# cpu.net
KiCad netlist of a schematic drawn in Altium Designer
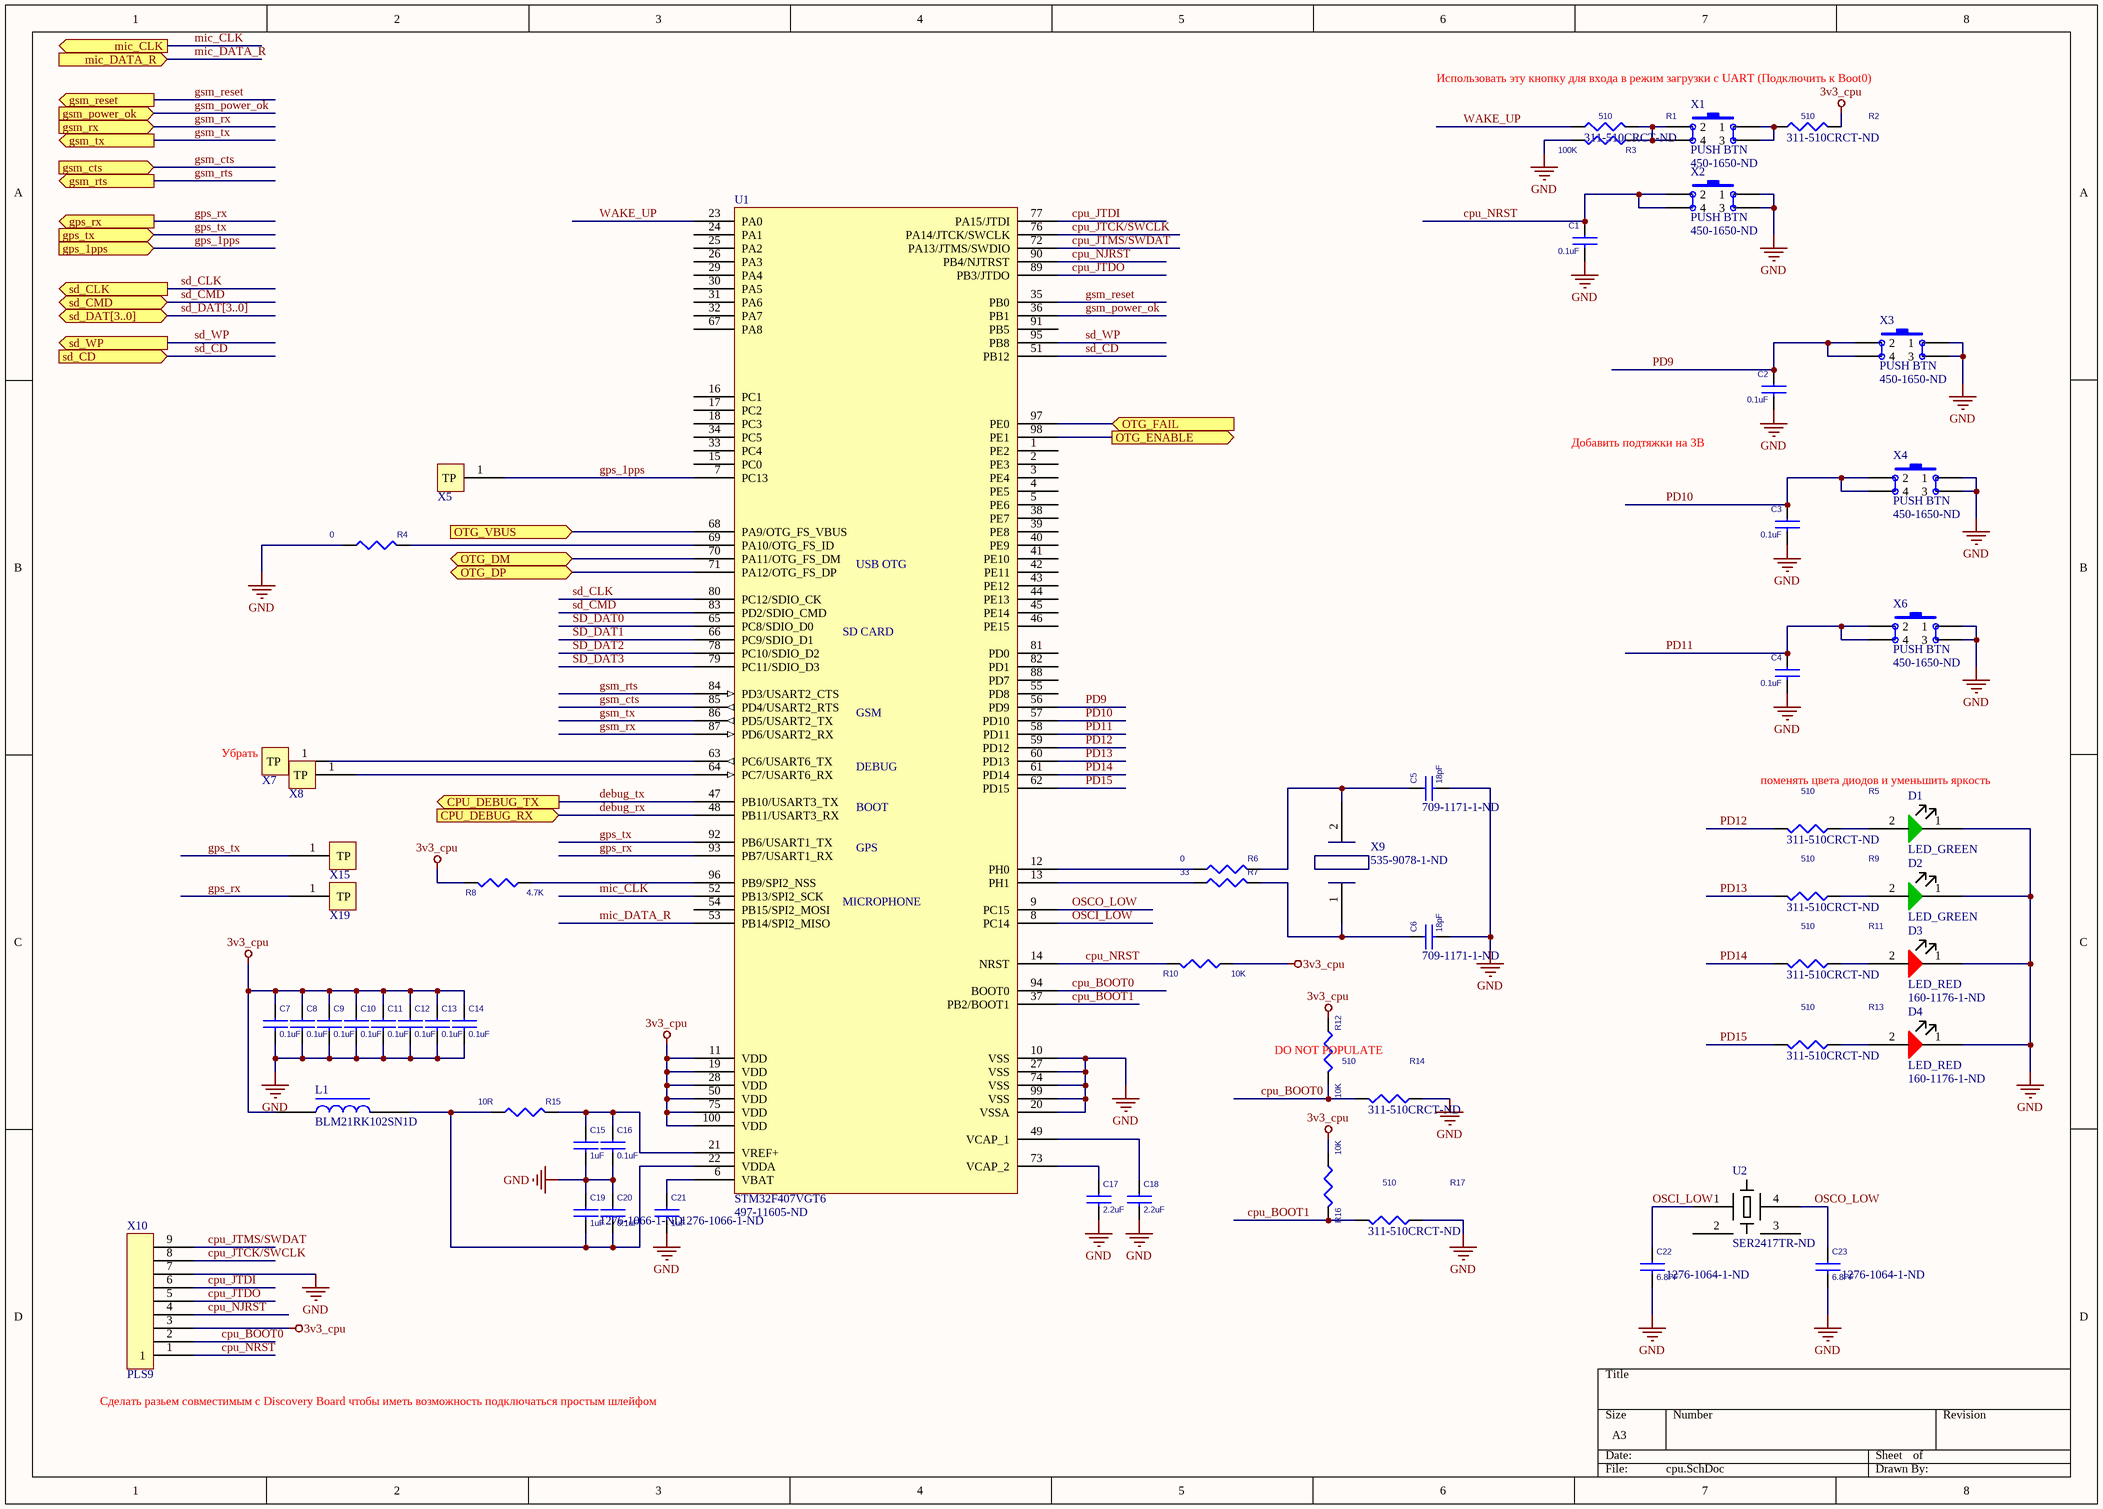
[diagram p0: cpu.SchDoc]

(export (version "E")
  (design (tool "Eeschema 10.0.6"))
  (components
    (comp (ref "C1")
      (value "0.1uF")
      (footprint "CAPC2012X09M")
      (description "CAP CER 0.1UF 25V 10% X7R 0805")
      (libsource (lib "Capacitors") (part "CAP_SMD_0.1UF_10%"))
    )
    (comp (ref "C2")
      (value "0.1uF")
      (footprint "CAPC2012X09M")
      (description "CAP CER 0.1UF 25V 10% X7R 0805")
      (libsource (lib "Capacitors") (part "CAP_SMD_0.1UF_10%"))
    )
    (comp (ref "C3")
      (value "0.1uF")
      (footprint "CAPC2012X09M")
      (description "CAP CER 0.1UF 25V 10% X7R 0805")
      (libsource (lib "Capacitors") (part "CAP_SMD_0.1UF_10%"))
    )
    (comp (ref "C4")
      (value "0.1uF")
      (footprint "CAPC2012X09M")
      (description "CAP CER 0.1UF 25V 10% X7R 0805")
      (libsource (lib "Capacitors") (part "CAP_SMD_0.1UF_10%"))
    )
    (comp (ref "C5")
      (value "18pF")
      (footprint "CAPC2012X09M")
      (description "CAP CER 27PF 200V 5% NP0 0805")
      (fields (field (name "SUPPLIER PART NUMBER 1") "709-1171-1-ND"))
      (libsource (lib "Capacitors") (part "CAP_SMD_18PF_5%"))
    )
    (comp (ref "C6")
      (value "18pF")
      (footprint "CAPC2012X09M")
      (description "CAP CER 27PF 200V 5% NP0 0805")
      (fields (field (name "SUPPLIER PART NUMBER 1") "709-1171-1-ND"))
      (libsource (lib "Capacitors") (part "CAP_SMD_18PF_5%"))
    )
    (comp (ref "C7")
      (value "0.1uF")
      (footprint "CAPC2012X09M")
      (description "CAP CER 0.1UF 25V 10% X7R 0805")
      (libsource (lib "Capacitors") (part "CAP_SMD_0.1UF_10%"))
    )
    (comp (ref "C8")
      (value "0.1uF")
      (footprint "CAPC2012X09M")
      (description "CAP CER 0.1UF 25V 10% X7R 0805")
      (libsource (lib "Capacitors") (part "CAP_SMD_0.1UF_10%"))
    )
    (comp (ref "C9")
      (value "0.1uF")
      (footprint "CAPC2012X09M")
      (description "CAP CER 0.1UF 25V 10% X7R 0805")
      (libsource (lib "Capacitors") (part "CAP_SMD_0.1UF_10%"))
    )
    (comp (ref "C10")
      (value "0.1uF")
      (footprint "CAPC2012X09M")
      (description "CAP CER 0.1UF 25V 10% X7R 0805")
      (libsource (lib "Capacitors") (part "CAP_SMD_0.1UF_10%"))
    )
    (comp (ref "C11")
      (value "0.1uF")
      (footprint "CAPC2012X09M")
      (description "CAP CER 0.1UF 25V 10% X7R 0805")
      (libsource (lib "Capacitors") (part "CAP_SMD_0.1UF_10%"))
    )
    (comp (ref "C12")
      (value "0.1uF")
      (footprint "CAPC2012X09M")
      (description "CAP CER 0.1UF 25V 10% X7R 0805")
      (libsource (lib "Capacitors") (part "CAP_SMD_0.1UF_10%"))
    )
    (comp (ref "C13")
      (value "0.1uF")
      (footprint "CAPC2012X09M")
      (description "CAP CER 0.1UF 25V 10% X7R 0805")
      (libsource (lib "Capacitors") (part "CAP_SMD_0.1UF_10%"))
    )
    (comp (ref "C14")
      (value "0.1uF")
      (footprint "CAPC2012X09M")
      (description "CAP CER 0.1UF 25V 10% X7R 0805")
      (libsource (lib "Capacitors") (part "CAP_SMD_0.1UF_10%"))
    )
    (comp (ref "C15")
      (value "1uF")
      (footprint "CAPC2012X09M")
      (description "MLCC; 1uF; 25V; X7R; ±10%; SMD; 0805;")
      (libsource (lib "Capacitors") (part "CAP_SMD_1uF_10%"))
    )
    (comp (ref "C16")
      (value "0.1uF")
      (footprint "CAPC2012X09M")
      (description "CAP CER 0.1UF 25V 10% X7R 0805")
      (libsource (lib "Capacitors") (part "CAP_SMD_0.1UF_10%"))
    )
    (comp (ref "C17")
      (value "2.2uF")
      (footprint "CAPC2012X09M")
      (description "CAP CER 2.2UF 16V 10% X5R 0805")
      (libsource (lib "Capacitors") (part "CAP_SMD_2.2uF_10%"))
    )
    (comp (ref "C18")
      (value "2.2uF")
      (footprint "CAPC2012X09M")
      (description "CAP CER 2.2UF 16V 10% X5R 0805")
      (libsource (lib "Capacitors") (part "CAP_SMD_2.2uF_10%"))
    )
    (comp (ref "C19")
      (value "1uF")
      (footprint "CAPC2012X09M")
      (description "MLCC; 1uF; 25V; X7R; ±10%; SMD; 0805;")
      (fields (field (name "SUPPLIER PART NUMBER 1") "1276-1066-1-ND"))
      (libsource (lib "Capacitors") (part "CAP_SMD_1uF_10%"))
    )
    (comp (ref "C20")
      (value "0.1uF")
      (footprint "CAPC2012X09M")
      (description "CAP CER 0.1UF 25V 10% X7R 0805")
      (libsource (lib "Capacitors") (part "CAP_SMD_0.1UF_10%"))
    )
    (comp (ref "C21")
      (value "1uF")
      (footprint "CAPC2012X09M")
      (description "MLCC; 1uF; 25V; X7R; ±10%; SMD; 0805;")
      (fields (field (name "SUPPLIER PART NUMBER 1") "1276-1066-1-ND"))
      (libsource (lib "Capacitors") (part "CAP_SMD_1uF_10%"))
    )
    (comp (ref "C22")
      (value "6.8PF")
      (footprint "CAPC2012X09M")
      (description "CAP MLCC 6.8PF 50V 5% NP0 0805")
      (fields (field (name "SUPPLIER PART NUMBER 1") "1276-1064-1-ND"))
      (libsource (lib "Capacitors") (part "CAP_SMD_6.8PF_5%"))
    )
    (comp (ref "C23")
      (value "6.8PF")
      (footprint "CAPC2012X09M")
      (description "CAP MLCC 6.8PF 50V 5% NP0 0805")
      (fields (field (name "SUPPLIER PART NUMBER 1") "1276-1064-1-ND"))
      (libsource (lib "Capacitors") (part "CAP_SMD_6.8PF_5%"))
    )
    (comp (ref "D1")
      (value "LED_GREEN")
      (footprint "DIOC2012X11N")
      (libsource (lib "Passive") (part "LED_GREEN"))
    )
    (comp (ref "D2")
      (value "LED_GREEN")
      (footprint "DIOC2012X11N")
      (libsource (lib "Passive") (part "LED_GREEN"))
    )
    (comp (ref "D3")
      (value "LED_RED")
      (footprint "DIOC2012X11N")
      (fields (field (name "SUPPLIER PART NUMBER 1") "160-1176-1-ND"))
      (libsource (lib "Passive") (part "LED_RED"))
    )
    (comp (ref "D4")
      (value "LED_RED")
      (footprint "DIOC2012X11N")
      (fields (field (name "SUPPLIER PART NUMBER 1") "160-1176-1-ND"))
      (libsource (lib "Passive") (part "LED_RED"))
    )
    (comp (ref "L1")
      (value "BLM21RK102SN1D")
      (footprint "DIOC2012X11N")
      (libsource (lib "Passive") (part "BLM21RK102SN1D"))
    )
    (comp (ref "R1")
      (value "510")
      (footprint "RESC2013X06M")
      (description "RES - 510 OHM, 5%, 1/8W, 0805 SMD")
      (fields (field (name "SUPPLIER PART NUMBER 1") "311-510CRCT-ND"))
      (libsource (lib "Resistors") (part "RES_SMD_510_5%"))
    )
    (comp (ref "R2")
      (value "510")
      (footprint "RESC2013X06M")
      (description "RES - 510 OHM, 5%, 1/8W, 0805 SMD")
      (fields (field (name "SUPPLIER PART NUMBER 1") "311-510CRCT-ND"))
      (libsource (lib "Resistors") (part "RES_SMD_510_5%"))
    )
    (comp (ref "R3")
      (value "100K")
      (footprint "RESC2013X06M")
      (description "RES - 100K OHM, 5%, 1/8W, 0805 SMD")
      (libsource (lib "Resistors") (part "RES_SMD_100K"))
    )
    (comp (ref "R4")
      (value "0")
      (footprint "RESC2013X06M")
      (description "RES 0.0 OHM 1/8W JUMP 0805 SMD")
      (libsource (lib "Resistors") (part "RES_SMD_0"))
    )
    (comp (ref "R5")
      (value "510")
      (footprint "RESC2013X06M")
      (description "RES - 510 OHM, 5%, 1/8W, 0805 SMD")
      (fields (field (name "SUPPLIER PART NUMBER 1") "311-510CRCT-ND"))
      (libsource (lib "Resistors") (part "RES_SMD_510_5%"))
    )
    (comp (ref "R6")
      (value "0")
      (footprint "RESC2013X06M")
      (description "RES 0.0 OHM 1/8W JUMP 0805 SMD")
      (libsource (lib "Resistors") (part "RES_SMD_0"))
    )
    (comp (ref "R7")
      (value "33")
      (footprint "RESC2013X06M")
      (description "RES - 33 OHM, 5%, 1/8W, 0805 SMD")
      (libsource (lib "Resistors") (part "RES_SMD_33R_5%"))
    )
    (comp (ref "R8")
      (value "4.7K")
      (footprint "RESC2013X06M")
      (description "RES 4.7K OHM 1/8W 1% 0805 SMD")
      (libsource (lib "Resistors") (part "RES_SMD_4.7K_1%"))
    )
    (comp (ref "R9")
      (value "510")
      (footprint "RESC2013X06M")
      (description "RES - 510 OHM, 5%, 1/8W, 0805 SMD")
      (fields (field (name "SUPPLIER PART NUMBER 1") "311-510CRCT-ND"))
      (libsource (lib "Resistors") (part "RES_SMD_510_5%"))
    )
    (comp (ref "R10")
      (value "10K")
      (footprint "RESC2013X06M")
      (description "RES 10K OHM 1/8W 5% 0805 SMD")
      (libsource (lib "Resistors") (part "RES_SMD_10K_5%"))
    )
    (comp (ref "R11")
      (value "510")
      (footprint "RESC2013X06M")
      (description "RES - 510 OHM, 5%, 1/8W, 0805 SMD")
      (fields (field (name "SUPPLIER PART NUMBER 1") "311-510CRCT-ND"))
      (libsource (lib "Resistors") (part "RES_SMD_510_5%"))
    )
    (comp (ref "R12")
      (value "10K")
      (footprint "RESC2013X06M")
      (description "RES 10K OHM 1/8W 5% 0805 SMD")
      (libsource (lib "Resistors") (part "RES_SMD_10K_5%"))
    )
    (comp (ref "R13")
      (value "510")
      (footprint "RESC2013X06M")
      (description "RES - 510 OHM, 5%, 1/8W, 0805 SMD")
      (fields (field (name "SUPPLIER PART NUMBER 1") "311-510CRCT-ND"))
      (libsource (lib "Resistors") (part "RES_SMD_510_5%"))
    )
    (comp (ref "R14")
      (value "510")
      (footprint "RESC2013X06M")
      (description "RES - 510 OHM, 5%, 1/8W, 0805 SMD")
      (fields (field (name "SUPPLIER PART NUMBER 1") "311-510CRCT-ND"))
      (libsource (lib "Resistors") (part "RES_SMD_510_5%"))
    )
    (comp (ref "R15")
      (value "10R")
      (footprint "RESC2013X06M")
      (description "RES 10 OHM 1/8W 1% 0805 SMD")
      (libsource (lib "Resistors") (part "RES_SMD_10R_5%"))
    )
    (comp (ref "R16")
      (value "10K")
      (footprint "RESC2013X06M")
      (description "RES 10K OHM 1/8W 5% 0805 SMD")
      (libsource (lib "Resistors") (part "RES_SMD_10K_5%"))
    )
    (comp (ref "R17")
      (value "510")
      (footprint "RESC2013X06M")
      (description "RES - 510 OHM, 5%, 1/8W, 0805 SMD")
      (fields (field (name "SUPPLIER PART NUMBER 1") "311-510CRCT-ND"))
      (libsource (lib "Resistors") (part "RES_SMD_510_5%"))
    )
    (comp (ref "U1")
      (value "STM32F407VGT6")
      (footprint "TSQFP50P1600X1600X160-100M")
      (fields (field (name "SUPPLIER PART NUMBER 1") "497-11605-ND"))
      (libsource (lib "TruthEar") (part "STM32F407VGT6"))
    )
    (comp (ref "U2")
      (value "32.768KHZ")
      (footprint "SOJ550P380X254-4M")
      (fields (field (name "SUPPLIER PART NUMBER 1") "SER2417TR-ND"))
      (libsource (lib "TruthEar") (part "MC-306"))
    )
    (comp (ref "X1")
      (value "PUSH BTN")
      (footprint "PUSHBTN")
      (fields (field (name "SUPPLIER PART NUMBER 1") "450-1650-ND"))
      (libsource (lib "TruthEar") (part "SW1"))
    )
    (comp (ref "X2")
      (value "PUSH BTN")
      (footprint "PUSHBTN")
      (fields (field (name "SUPPLIER PART NUMBER 1") "450-1650-ND"))
      (libsource (lib "TruthEar") (part "SW1"))
    )
    (comp (ref "X3")
      (value "PUSH BTN")
      (footprint "PUSHBTN")
      (fields (field (name "SUPPLIER PART NUMBER 1") "450-1650-ND"))
      (libsource (lib "TruthEar") (part "SW1"))
    )
    (comp (ref "X4")
      (value "PUSH BTN")
      (footprint "PUSHBTN")
      (fields (field (name "SUPPLIER PART NUMBER 1") "450-1650-ND"))
      (libsource (lib "TruthEar") (part "SW1"))
    )
    (comp (ref "X5") (value "TestPoint") (footprint "TP") (libsource (lib "") (part "TestPoint_2")))
    (comp (ref "X6")
      (value "PUSH BTN")
      (footprint "PUSHBTN")
      (fields (field (name "SUPPLIER PART NUMBER 1") "450-1650-ND"))
      (libsource (lib "TruthEar") (part "SW1"))
    )
    (comp (ref "X7") (value "TestPoint") (footprint "TP") (libsource (lib "Passive") (part "TestPoint")))
    (comp (ref "X8") (value "TestPoint") (footprint "TP") (libsource (lib "Passive") (part "TestPoint")))
    (comp (ref "X9")
      (value "25.000Mhz")
      (footprint "SODFL1270X420-2L")
      (fields (field (name "SUPPLIER PART NUMBER 1") "535-9078-1-ND"))
      (libsource (lib "TruthEar") (part "OSC25M"))
    )
    (comp (ref "X10") (value "PLS9") (footprint "PLS9") (libsource (lib "Connectors") (part "PLS9")))
    (comp (ref "X15") (value "TestPoint") (footprint "TP") (libsource (lib "") (part "TestPoint_1")))
    (comp (ref "X19") (value "TestPoint") (footprint "TP") (libsource (lib "") (part "TestPoint_1")))
  )
  (nets
    (net (code "5") (name "/OSCI_LOW") (class "Default")
      (node (ref "C22") (pin "1") (pinfunction "1_1") (pintype "passive"))
      (node (ref "U1") (pin "8") (pinfunction "PC14_8") (pintype "passive"))
      (node (ref "U2") (pin "1") (pinfunction "OSC1_1") (pintype "power_in"))
    )
    (net (code "6") (name "/OSCO_LOW") (class "Default")
      (node (ref "C23") (pin "1") (pinfunction "1_1") (pintype "passive"))
      (node (ref "U1") (pin "9") (pinfunction "PC15_9") (pintype "passive"))
      (node (ref "U2") (pin "4") (pinfunction "OSC2_4") (pintype "power_in"))
    )
    (net (code "7") (name "/OTG_DM") (class "Default")
      (node (ref "U1") (pin "70") (pinfunction "PA11/OTG_FS_DM_70") (pintype "passive"))
    )
    (net (code "8") (name "/OTG_DP") (class "Default")
      (node (ref "U1") (pin "71") (pinfunction "PA12/OTG_FS_DP_71") (pintype "passive"))
    )
    (net (code "9") (name "/OTG_ENABLE") (class "Default")
      (node (ref "U1") (pin "98") (pinfunction "PE1_98") (pintype "passive"))
    )
    (net (code "10") (name "/OTG_FAIL") (class "Default")
      (node (ref "U1") (pin "97") (pinfunction "PE0_97") (pintype "passive"))
    )
    (net (code "11") (name "/OTG_VBUS") (class "Default")
      (node (ref "U1") (pin "68") (pinfunction "PA9/OTG_FS_VBUS_68") (pintype "passive"))
    )
    (net (code "12") (name "/PD9") (class "Default")
      (node (ref "C2") (pin "1") (pinfunction "1_1") (pintype "passive"))
      (node (ref "U1") (pin "56") (pinfunction "PD9_56") (pintype "passive"))
      (node (ref "X3") (pin "2") (pinfunction "2_2") (pintype "passive"))
      (node (ref "X3") (pin "4") (pinfunction "4_4") (pintype "passive"))
    )
    (net (code "13") (name "/PD10") (class "Default")
      (node (ref "C3") (pin "1") (pinfunction "1_1") (pintype "passive"))
      (node (ref "U1") (pin "57") (pinfunction "PD10_57") (pintype "passive"))
      (node (ref "X4") (pin "2") (pinfunction "2_2") (pintype "passive"))
      (node (ref "X4") (pin "4") (pinfunction "4_4") (pintype "passive"))
    )
    (net (code "14") (name "/PD11") (class "Default")
      (node (ref "C4") (pin "1") (pinfunction "1_1") (pintype "passive"))
      (node (ref "U1") (pin "58") (pinfunction "PD11_58") (pintype "passive"))
      (node (ref "X6") (pin "2") (pinfunction "2_2") (pintype "passive"))
      (node (ref "X6") (pin "4") (pinfunction "4_4") (pintype "passive"))
    )
    (net (code "15") (name "/PD12") (class "Default")
      (node (ref "R5") (pin "2") (pinfunction "2_2") (pintype "passive"))
      (node (ref "U1") (pin "59") (pinfunction "PD12_59") (pintype "passive"))
    )
    (net (code "16") (name "/PD13") (class "Default")
      (node (ref "R9") (pin "2") (pinfunction "2_2") (pintype "passive"))
      (node (ref "U1") (pin "60") (pinfunction "PD13_60") (pintype "passive"))
    )
    (net (code "17") (name "/PD14") (class "Default")
      (node (ref "R11") (pin "2") (pinfunction "2_2") (pintype "passive"))
      (node (ref "U1") (pin "61") (pinfunction "PD14_61") (pintype "passive"))
    )
    (net (code "18") (name "/PD15") (class "Default")
      (node (ref "R13") (pin "2") (pinfunction "2_2") (pintype "passive"))
      (node (ref "U1") (pin "62") (pinfunction "PD15_62") (pintype "passive"))
    )
    (net (code "19") (name "/SD_DAT0") (class "Default")
      (node (ref "U1") (pin "65") (pinfunction "PC8/SDIO_D0_65") (pintype "passive"))
    )
    (net (code "20") (name "/SD_DAT1") (class "Default")
      (node (ref "U1") (pin "66") (pinfunction "PC9/SDIO_D1_66") (pintype "passive"))
    )
    (net (code "21") (name "/SD_DAT2") (class "Default")
      (node (ref "U1") (pin "78") (pinfunction "PC10/SDIO_D2_78") (pintype "passive"))
    )
    (net (code "22") (name "/SD_DAT3") (class "Default")
      (node (ref "U1") (pin "79") (pinfunction "PC11/SDIO_D3_79") (pintype "passive"))
    )
    (net (code "23") (name "/WAKE_UP") (class "Default")
      (node (ref "R1") (pin "2") (pinfunction "2_2") (pintype "passive"))
      (node (ref "U1") (pin "23") (pinfunction "PA0_23") (pintype "passive"))
    )
    (net (code "24") (name "/cpu_BOOT0") (class "Default")
      (node (ref "R12") (pin "1") (pinfunction "1_1") (pintype "passive"))
      (node (ref "R14") (pin "1") (pinfunction "1_1") (pintype "passive"))
      (node (ref "U1") (pin "94") (pinfunction "BOOT0_94") (pintype "passive"))
      (node (ref "X10") (pin "2") (pinfunction "2_2") (pintype "power_in"))
    )
    (net (code "25") (name "/cpu_BOOT1") (class "Default")
      (node (ref "R16") (pin "2") (pinfunction "2_2") (pintype "passive"))
      (node (ref "R17") (pin "2") (pinfunction "2_2") (pintype "passive"))
      (node (ref "U1") (pin "37") (pinfunction "PB2/BOOT1_37") (pintype "passive"))
    )
    (net (code "26") (name "/cpu_JTCK{slash}SWCLK") (class "Default")
      (node (ref "U1") (pin "76") (pinfunction "PA14/JTCK/SWCLK_76") (pintype "passive"))
      (node (ref "X10") (pin "8") (pinfunction "8_8") (pintype "power_in"))
    )
    (net (code "27") (name "/cpu_JTDI") (class "Default")
      (node (ref "U1") (pin "77") (pinfunction "PA15/JTDI_77") (pintype "passive"))
      (node (ref "X10") (pin "6") (pinfunction "6_6") (pintype "power_in"))
    )
    (net (code "28") (name "/cpu_JTDO") (class "Default")
      (node (ref "U1") (pin "89") (pinfunction "PB3/JTDO_89") (pintype "passive"))
      (node (ref "X10") (pin "5") (pinfunction "5_5") (pintype "power_in"))
    )
    (net (code "29") (name "/cpu_JTMS{slash}SWDAT") (class "Default")
      (node (ref "U1") (pin "72") (pinfunction "PA13/JTMS/SWDIO_72") (pintype "passive"))
      (node (ref "X10") (pin "9") (pinfunction "9_9") (pintype "power_in"))
    )
    (net (code "30") (name "/cpu_NJRST") (class "Default")
      (node (ref "U1") (pin "90") (pinfunction "PB4/NJTRST_90") (pintype "passive"))
      (node (ref "X10") (pin "4") (pinfunction "4_4") (pintype "power_in"))
    )
    (net (code "31") (name "/cpu_NRST") (class "Default")
      (node (ref "C1") (pin "1") (pinfunction "1_1") (pintype "passive"))
      (node (ref "R10") (pin "2") (pinfunction "2_2") (pintype "passive"))
      (node (ref "U1") (pin "14") (pinfunction "NRST_14") (pintype "passive"))
      (node (ref "X10") (pin "1") (pinfunction "1_1") (pintype "power_in"))
      (node (ref "X2") (pin "2") (pinfunction "2_2") (pintype "passive"))
      (node (ref "X2") (pin "4") (pinfunction "4_4") (pintype "passive"))
    )
    (net (code "32") (name "/debug_rx") (class "Default")
      (node (ref "U1") (pin "48") (pinfunction "PB11/USART3_RX_48") (pintype "passive"))
    )
    (net (code "33") (name "/debug_tx") (class "Default")
      (node (ref "U1") (pin "47") (pinfunction "PB10/USART3_TX_47") (pintype "passive"))
    )
    (net (code "34") (name "/gps_1pps") (class "Default")
      (node (ref "U1") (pin "7") (pinfunction "PC13_7") (pintype "passive"))
      (node (ref "X5") (pin "1") (pinfunction "TP_1") (pintype "power_in"))
    )
    (net (code "35") (name "/gps_rx") (class "Default")
      (node (ref "U1") (pin "93") (pinfunction "PB7/USART1_RX_93") (pintype "passive"))
      (node (ref "X19") (pin "1") (pinfunction "TP_1") (pintype "power_in"))
    )
    (net (code "36") (name "/gps_tx") (class "Default")
      (node (ref "U1") (pin "92") (pinfunction "PB6/USART1_TX_92") (pintype "passive"))
      (node (ref "X15") (pin "1") (pinfunction "TP_1") (pintype "power_in"))
    )
    (net (code "37") (name "/gsm_cts") (class "Default")
      (node (ref "U1") (pin "85") (pinfunction "PD4/USART2_RTS_85") (pintype "output"))
    )
    (net (code "38") (name "/gsm_power_ok") (class "Default")
      (node (ref "U1") (pin "36") (pinfunction "PB1_36") (pintype "passive"))
    )
    (net (code "39") (name "/gsm_reset") (class "Default")
      (node (ref "U1") (pin "35") (pinfunction "PB0_35") (pintype "passive"))
    )
    (net (code "40") (name "/gsm_rts") (class "Default")
      (node (ref "U1") (pin "84") (pinfunction "PD3/USART2_CTS_84") (pintype "input"))
    )
    (net (code "41") (name "/gsm_rx") (class "Default")
      (node (ref "U1") (pin "87") (pinfunction "PD6/USART2_RX_87") (pintype "input"))
    )
    (net (code "42") (name "/gsm_tx") (class "Default")
      (node (ref "U1") (pin "86") (pinfunction "PD5/USART2_TX_86") (pintype "output"))
    )
    (net (code "43") (name "/mic_CLK") (class "Default")
      (node (ref "U1") (pin "52") (pinfunction "PB13/SPI2_SCK_52") (pintype "passive"))
    )
    (net (code "44") (name "/mic_DATA_R") (class "Default")
      (node (ref "U1") (pin "53") (pinfunction "PB14/SPI2_MISO_53") (pintype "passive"))
    )
    (net (code "45") (name "/sd_CD") (class "Default")
      (node (ref "U1") (pin "51") (pinfunction "PB12_51") (pintype "passive"))
    )
    (net (code "46") (name "/sd_CLK") (class "Default")
      (node (ref "U1") (pin "80") (pinfunction "PC12/SDIO_CK_80") (pintype "passive"))
    )
    (net (code "47") (name "/sd_CMD") (class "Default")
      (node (ref "U1") (pin "83") (pinfunction "PD2/SDIO_CMD_83") (pintype "passive"))
    )
    (net (code "49") (name "/sd_WP") (class "Default")
      (node (ref "U1") (pin "95") (pinfunction "PB8_95") (pintype "passive"))
    )
    (net (code "50") (name "3v3_cpu") (class "Default")
      (node (ref "C10") (pin "1") (pinfunction "1_1") (pintype "passive"))
      (node (ref "C11") (pin "1") (pinfunction "1_1") (pintype "passive"))
      (node (ref "C12") (pin "1") (pinfunction "1_1") (pintype "passive"))
      (node (ref "C13") (pin "1") (pinfunction "1_1") (pintype "passive"))
      (node (ref "C14") (pin "1") (pinfunction "1_1") (pintype "passive"))
      (node (ref "C7") (pin "1") (pinfunction "1_1") (pintype "passive"))
      (node (ref "C8") (pin "1") (pinfunction "1_1") (pintype "passive"))
      (node (ref "C9") (pin "1") (pinfunction "1_1") (pintype "passive"))
      (node (ref "L1") (pin "1") (pinfunction "1_1") (pintype "passive"))
      (node (ref "R10") (pin "1") (pinfunction "1_1") (pintype "passive"))
      (node (ref "R12") (pin "2") (pinfunction "2_2") (pintype "passive"))
      (node (ref "R16") (pin "1") (pinfunction "1_1") (pintype "passive"))
      (node (ref "R2") (pin "1") (pinfunction "1_1") (pintype "passive"))
      (node (ref "R8") (pin "2") (pinfunction "2_2") (pintype "passive"))
      (node (ref "U1") (pin "100") (pinfunction "VDD_100") (pintype "passive"))
      (node (ref "U1") (pin "11") (pinfunction "VDD_11") (pintype "passive"))
      (node (ref "U1") (pin "19") (pinfunction "VDD_19") (pintype "passive"))
      (node (ref "U1") (pin "28") (pinfunction "VDD_28") (pintype "passive"))
      (node (ref "U1") (pin "50") (pinfunction "VDD_50") (pintype "passive"))
      (node (ref "U1") (pin "75") (pinfunction "VDD_75") (pintype "passive"))
      (node (ref "X10") (pin "3") (pinfunction "3_3") (pintype "power_in"))
    )
    (net (code "51") (name "GND") (class "Default")
      (node (ref "C1") (pin "2") (pinfunction "2_2") (pintype "passive"))
      (node (ref "C10") (pin "2") (pinfunction "2_2") (pintype "passive"))
      (node (ref "C11") (pin "2") (pinfunction "2_2") (pintype "passive"))
      (node (ref "C12") (pin "2") (pinfunction "2_2") (pintype "passive"))
      (node (ref "C13") (pin "2") (pinfunction "2_2") (pintype "passive"))
      (node (ref "C14") (pin "2") (pinfunction "2_2") (pintype "passive"))
      (node (ref "C15") (pin "2") (pinfunction "2_2") (pintype "passive"))
      (node (ref "C16") (pin "2") (pinfunction "2_2") (pintype "passive"))
      (node (ref "C17") (pin "2") (pinfunction "2_2") (pintype "passive"))
      (node (ref "C18") (pin "2") (pinfunction "2_2") (pintype "passive"))
      (node (ref "C19") (pin "1") (pinfunction "1_1") (pintype "passive"))
      (node (ref "C2") (pin "2") (pinfunction "2_2") (pintype "passive"))
      (node (ref "C20") (pin "1") (pinfunction "1_1") (pintype "passive"))
      (node (ref "C21") (pin "2") (pinfunction "2_2") (pintype "passive"))
      (node (ref "C22") (pin "2") (pinfunction "2_2") (pintype "passive"))
      (node (ref "C23") (pin "2") (pinfunction "2_2") (pintype "passive"))
      (node (ref "C3") (pin "2") (pinfunction "2_2") (pintype "passive"))
      (node (ref "C4") (pin "2") (pinfunction "2_2") (pintype "passive"))
      (node (ref "C5") (pin "2") (pinfunction "2_2") (pintype "passive"))
      (node (ref "C6") (pin "2") (pinfunction "2_2") (pintype "passive"))
      (node (ref "C7") (pin "2") (pinfunction "2_2") (pintype "passive"))
      (node (ref "C8") (pin "2") (pinfunction "2_2") (pintype "passive"))
      (node (ref "C9") (pin "2") (pinfunction "2_2") (pintype "passive"))
      (node (ref "D1") (pin "1") (pinfunction "C_1") (pintype "passive"))
      (node (ref "D2") (pin "1") (pinfunction "C_1") (pintype "passive"))
      (node (ref "D3") (pin "1") (pinfunction "C_1") (pintype "passive"))
      (node (ref "D4") (pin "1") (pinfunction "C_1") (pintype "passive"))
      (node (ref "R14") (pin "2") (pinfunction "2_2") (pintype "passive"))
      (node (ref "R17") (pin "1") (pinfunction "1_1") (pintype "passive"))
      (node (ref "R3") (pin "1") (pinfunction "1_1") (pintype "passive"))
      (node (ref "R4") (pin "1") (pinfunction "1_1") (pintype "passive"))
      (node (ref "U1") (pin "10") (pinfunction "VSS_10") (pintype "passive"))
      (node (ref "U1") (pin "20") (pinfunction "VSSA_20") (pintype "passive"))
      (node (ref "U1") (pin "27") (pinfunction "VSS_27") (pintype "passive"))
      (node (ref "U1") (pin "74") (pinfunction "VSS_74") (pintype "passive"))
      (node (ref "U1") (pin "99") (pinfunction "VSS_99") (pintype "passive"))
      (node (ref "X10") (pin "7") (pinfunction "7_7") (pintype "power_in"))
      (node (ref "X2") (pin "1") (pinfunction "1_1") (pintype "passive"))
      (node (ref "X2") (pin "3") (pinfunction "3_3") (pintype "passive"))
      (node (ref "X3") (pin "1") (pinfunction "1_1") (pintype "passive"))
      (node (ref "X3") (pin "3") (pinfunction "3_3") (pintype "passive"))
      (node (ref "X4") (pin "1") (pinfunction "1_1") (pintype "passive"))
      (node (ref "X4") (pin "3") (pinfunction "3_3") (pintype "passive"))
      (node (ref "X6") (pin "1") (pinfunction "1_1") (pintype "passive"))
      (node (ref "X6") (pin "3") (pinfunction "3_3") (pintype "passive"))
    )
    (net (code "52") (name "Net-(C5-Pad1)") (class "Default")
      (node (ref "C5") (pin "1") (pinfunction "1_1") (pintype "passive"))
      (node (ref "R6") (pin "2") (pinfunction "2_2") (pintype "passive"))
      (node (ref "X9") (pin "2") (pinfunction "2_2") (pintype "power_in"))
    )
    (net (code "53") (name "Net-(C6-Pad1)") (class "Default")
      (node (ref "C6") (pin "1") (pinfunction "1_1") (pintype "passive"))
      (node (ref "R7") (pin "2") (pinfunction "2_2") (pintype "passive"))
      (node (ref "X9") (pin "1") (pinfunction "1_1") (pintype "power_in"))
    )
    (net (code "54") (name "Net-(D1-A)") (class "Default")
      (node (ref "D1") (pin "2") (pinfunction "A_2") (pintype "passive"))
      (node (ref "R5") (pin "1") (pinfunction "1_1") (pintype "passive"))
    )
    (net (code "55") (name "Net-(D2-A)") (class "Default")
      (node (ref "D2") (pin "2") (pinfunction "A_2") (pintype "passive"))
      (node (ref "R9") (pin "1") (pinfunction "1_1") (pintype "passive"))
    )
    (net (code "56") (name "Net-(D3-A)") (class "Default")
      (node (ref "D3") (pin "2") (pinfunction "A_2") (pintype "passive"))
      (node (ref "R11") (pin "1") (pinfunction "1_1") (pintype "passive"))
    )
    (net (code "57") (name "Net-(D4-A)") (class "Default")
      (node (ref "D4") (pin "2") (pinfunction "A_2") (pintype "passive"))
      (node (ref "R13") (pin "1") (pinfunction "1_1") (pintype "passive"))
    )
    (net (code "58") (name "Net-(R1-Pad1)") (class "Default")
      (node (ref "R1") (pin "1") (pinfunction "1_1") (pintype "passive"))
      (node (ref "R3") (pin "2") (pinfunction "2_2") (pintype "passive"))
      (node (ref "X1") (pin "2") (pinfunction "2_2") (pintype "passive"))
      (node (ref "X1") (pin "4") (pinfunction "4_4") (pintype "passive"))
    )
    (net (code "59") (name "Net-(R2-Pad2)") (class "Default")
      (node (ref "R2") (pin "2") (pinfunction "2_2") (pintype "passive"))
      (node (ref "X1") (pin "1") (pinfunction "1_1") (pintype "passive"))
      (node (ref "X1") (pin "3") (pinfunction "3_3") (pintype "passive"))
    )
    (net (code "60") (name "Net-(U1-PA10{slash}OTG_FS_ID)") (class "Default")
      (node (ref "R4") (pin "2") (pinfunction "2_2") (pintype "passive"))
      (node (ref "U1") (pin "69") (pinfunction "PA10/OTG_FS_ID_69") (pintype "passive"))
    )
    (net (code "61") (name "Net-(U1-PB9{slash}SPI2_NSS)") (class "Default")
      (node (ref "R8") (pin "1") (pinfunction "1_1") (pintype "passive"))
      (node (ref "U1") (pin "96") (pinfunction "PB9/SPI2_NSS_96") (pintype "passive"))
    )
    (net (code "62") (name "Net-(U1-PC6{slash}USART6_TX)") (class "Default")
      (node (ref "U1") (pin "63") (pinfunction "PC6/USART6_TX_63") (pintype "output"))
      (node (ref "X7") (pin "1") (pinfunction "TP_1") (pintype "power_in"))
    )
    (net (code "63") (name "Net-(U1-PC7{slash}USART6_RX)") (class "Default")
      (node (ref "U1") (pin "64") (pinfunction "PC7/USART6_RX_64") (pintype "input"))
      (node (ref "X8") (pin "1") (pinfunction "TP_1") (pintype "power_in"))
    )
    (net (code "64") (name "Net-(U1-PH0)") (class "Default")
      (node (ref "R6") (pin "1") (pinfunction "1_1") (pintype "passive"))
      (node (ref "U1") (pin "12") (pinfunction "PH0_12") (pintype "passive"))
    )
    (net (code "65") (name "Net-(U1-PH1)") (class "Default")
      (node (ref "R7") (pin "1") (pinfunction "1_1") (pintype "passive"))
      (node (ref "U1") (pin "13") (pinfunction "PH1_13") (pintype "passive"))
    )
    (net (code "66") (name "Net-(U1-VBAT)") (class "Default")
      (node (ref "C21") (pin "1") (pinfunction "1_1") (pintype "passive"))
      (node (ref "U1") (pin "6") (pinfunction "VBAT_6") (pintype "passive"))
    )
    (net (code "67") (name "Net-(U1-VCAP_1)") (class "Default")
      (node (ref "C18") (pin "1") (pinfunction "1_1") (pintype "passive"))
      (node (ref "U1") (pin "49") (pinfunction "VCAP_1_49") (pintype "passive"))
    )
    (net (code "68") (name "Net-(U1-VCAP_2)") (class "Default")
      (node (ref "C17") (pin "1") (pinfunction "1_1") (pintype "passive"))
      (node (ref "U1") (pin "73") (pinfunction "VCAP_2_73") (pintype "passive"))
    )
    (net (code "69") (name "Net-(U1-VDDA)") (class "Default")
      (node (ref "C19") (pin "2") (pinfunction "2_2") (pintype "passive"))
      (node (ref "C20") (pin "2") (pinfunction "2_2") (pintype "passive"))
      (node (ref "L1") (pin "2") (pinfunction "2_2") (pintype "passive"))
      (node (ref "R15") (pin "1") (pinfunction "1_1") (pintype "passive"))
      (node (ref "U1") (pin "22") (pinfunction "VDDA_22") (pintype "passive"))
    )
    (net (code "70") (name "Net-(U1-VREF+)") (class "Default")
      (node (ref "C15") (pin "1") (pinfunction "1_1") (pintype "passive"))
      (node (ref "C16") (pin "1") (pinfunction "1_1") (pintype "passive"))
      (node (ref "R15") (pin "2") (pinfunction "2_2") (pintype "passive"))
      (node (ref "U1") (pin "21") (pinfunction "VREF+_21") (pintype "passive"))
    )
    (net (code "71") (name "unconnected-(U1-PA1-Pad24)") (class "Default")
      (node (ref "U1") (pin "24") (pinfunction "PA1_24") (pintype "passive"))
    )
    (net (code "72") (name "unconnected-(U1-PA2-Pad25)") (class "Default")
      (node (ref "U1") (pin "25") (pinfunction "PA2_25") (pintype "passive"))
    )
    (net (code "73") (name "unconnected-(U1-PA3-Pad26)") (class "Default")
      (node (ref "U1") (pin "26") (pinfunction "PA3_26") (pintype "passive"))
    )
    (net (code "74") (name "unconnected-(U1-PA4-Pad29)") (class "Default")
      (node (ref "U1") (pin "29") (pinfunction "PA4_29") (pintype "passive"))
    )
    (net (code "75") (name "unconnected-(U1-PA5-Pad30)") (class "Default")
      (node (ref "U1") (pin "30") (pinfunction "PA5_30") (pintype "passive"))
    )
    (net (code "76") (name "unconnected-(U1-PA6-Pad31)") (class "Default")
      (node (ref "U1") (pin "31") (pinfunction "PA6_31") (pintype "passive"))
    )
    (net (code "77") (name "unconnected-(U1-PA7-Pad32)") (class "Default")
      (node (ref "U1") (pin "32") (pinfunction "PA7_32") (pintype "passive"))
    )
    (net (code "78") (name "unconnected-(U1-PA8-Pad67)") (class "Default")
      (node (ref "U1") (pin "67") (pinfunction "PA8_67") (pintype "passive"))
    )
    (net (code "79") (name "unconnected-(U1-PB5-Pad91)") (class "Default")
      (node (ref "U1") (pin "91") (pinfunction "PB5_91") (pintype "passive"))
    )
    (net (code "80") (name "unconnected-(U1-PB15{slash}SPI2_MOSI-Pad54)") (class "Default")
      (node (ref "U1") (pin "54") (pinfunction "PB15/SPI2_MOSI_54") (pintype "passive"))
    )
    (net (code "81") (name "unconnected-(U1-PC0-Pad15)") (class "Default")
      (node (ref "U1") (pin "15") (pinfunction "PC0_15") (pintype "passive"))
    )
    (net (code "82") (name "unconnected-(U1-PC1-Pad16)") (class "Default")
      (node (ref "U1") (pin "16") (pinfunction "PC1_16") (pintype "passive"))
    )
    (net (code "83") (name "unconnected-(U1-PC2-Pad17)") (class "Default")
      (node (ref "U1") (pin "17") (pinfunction "PC2_17") (pintype "passive"))
    )
    (net (code "84") (name "unconnected-(U1-PC3-Pad18)") (class "Default")
      (node (ref "U1") (pin "18") (pinfunction "PC3_18") (pintype "passive"))
    )
    (net (code "85") (name "unconnected-(U1-PC4-Pad33)") (class "Default")
      (node (ref "U1") (pin "33") (pinfunction "PC4_33") (pintype "passive"))
    )
    (net (code "86") (name "unconnected-(U1-PC5-Pad34)") (class "Default")
      (node (ref "U1") (pin "34") (pinfunction "PC5_34") (pintype "passive"))
    )
    (net (code "87") (name "unconnected-(U1-PD0-Pad81)") (class "Default")
      (node (ref "U1") (pin "81") (pinfunction "PD0_81") (pintype "passive"))
    )
    (net (code "88") (name "unconnected-(U1-PD1-Pad82)") (class "Default")
      (node (ref "U1") (pin "82") (pinfunction "PD1_82") (pintype "passive"))
    )
    (net (code "89") (name "unconnected-(U1-PD7-Pad88)") (class "Default")
      (node (ref "U1") (pin "88") (pinfunction "PD7_88") (pintype "passive"))
    )
    (net (code "90") (name "unconnected-(U1-PD8-Pad55)") (class "Default")
      (node (ref "U1") (pin "55") (pinfunction "PD8_55") (pintype "passive"))
    )
    (net (code "91") (name "unconnected-(U1-PE2-Pad1)") (class "Default")
      (node (ref "U1") (pin "1") (pinfunction "PE2_1") (pintype "passive"))
    )
    (net (code "92") (name "unconnected-(U1-PE3-Pad2)") (class "Default")
      (node (ref "U1") (pin "2") (pinfunction "PE3_2") (pintype "passive"))
    )
    (net (code "93") (name "unconnected-(U1-PE4-Pad3)") (class "Default")
      (node (ref "U1") (pin "3") (pinfunction "PE4_3") (pintype "passive"))
    )
    (net (code "94") (name "unconnected-(U1-PE5-Pad4)") (class "Default")
      (node (ref "U1") (pin "4") (pinfunction "PE5_4") (pintype "passive"))
    )
    (net (code "95") (name "unconnected-(U1-PE6-Pad5)") (class "Default")
      (node (ref "U1") (pin "5") (pinfunction "PE6_5") (pintype "passive"))
    )
    (net (code "96") (name "unconnected-(U1-PE7-Pad38)") (class "Default")
      (node (ref "U1") (pin "38") (pinfunction "PE7_38") (pintype "passive"))
    )
    (net (code "97") (name "unconnected-(U1-PE8-Pad39)") (class "Default")
      (node (ref "U1") (pin "39") (pinfunction "PE8_39") (pintype "passive"))
    )
    (net (code "98") (name "unconnected-(U1-PE9-Pad40)") (class "Default")
      (node (ref "U1") (pin "40") (pinfunction "PE9_40") (pintype "passive"))
    )
    (net (code "99") (name "unconnected-(U1-PE10-Pad41)") (class "Default")
      (node (ref "U1") (pin "41") (pinfunction "PE10_41") (pintype "passive"))
    )
    (net (code "100") (name "unconnected-(U1-PE11-Pad42)") (class "Default")
      (node (ref "U1") (pin "42") (pinfunction "PE11_42") (pintype "passive"))
    )
    (net (code "101") (name "unconnected-(U1-PE12-Pad43)") (class "Default")
      (node (ref "U1") (pin "43") (pinfunction "PE12_43") (pintype "passive"))
    )
    (net (code "102") (name "unconnected-(U1-PE13-Pad44)") (class "Default")
      (node (ref "U1") (pin "44") (pinfunction "PE13_44") (pintype "passive"))
    )
    (net (code "103") (name "unconnected-(U1-PE14-Pad45)") (class "Default")
      (node (ref "U1") (pin "45") (pinfunction "PE14_45") (pintype "passive"))
    )
    (net (code "104") (name "unconnected-(U1-PE15-Pad46)") (class "Default")
      (node (ref "U1") (pin "46") (pinfunction "PE15_46") (pintype "passive"))
    )
    (net (code "105") (name "unconnected-(U2-NC-Pad2)") (class "Default")
      (node (ref "U2") (pin "2") (pinfunction "NC_2") (pintype "power_in"))
    )
    (net (code "106") (name "unconnected-(U2-NC-Pad3)") (class "Default")
      (node (ref "U2") (pin "3") (pinfunction "NC_3") (pintype "power_in"))
    )
  )
)
